# MCU009A_ADC.net
KiCad netlist of a schematic drawn in Altium Designer
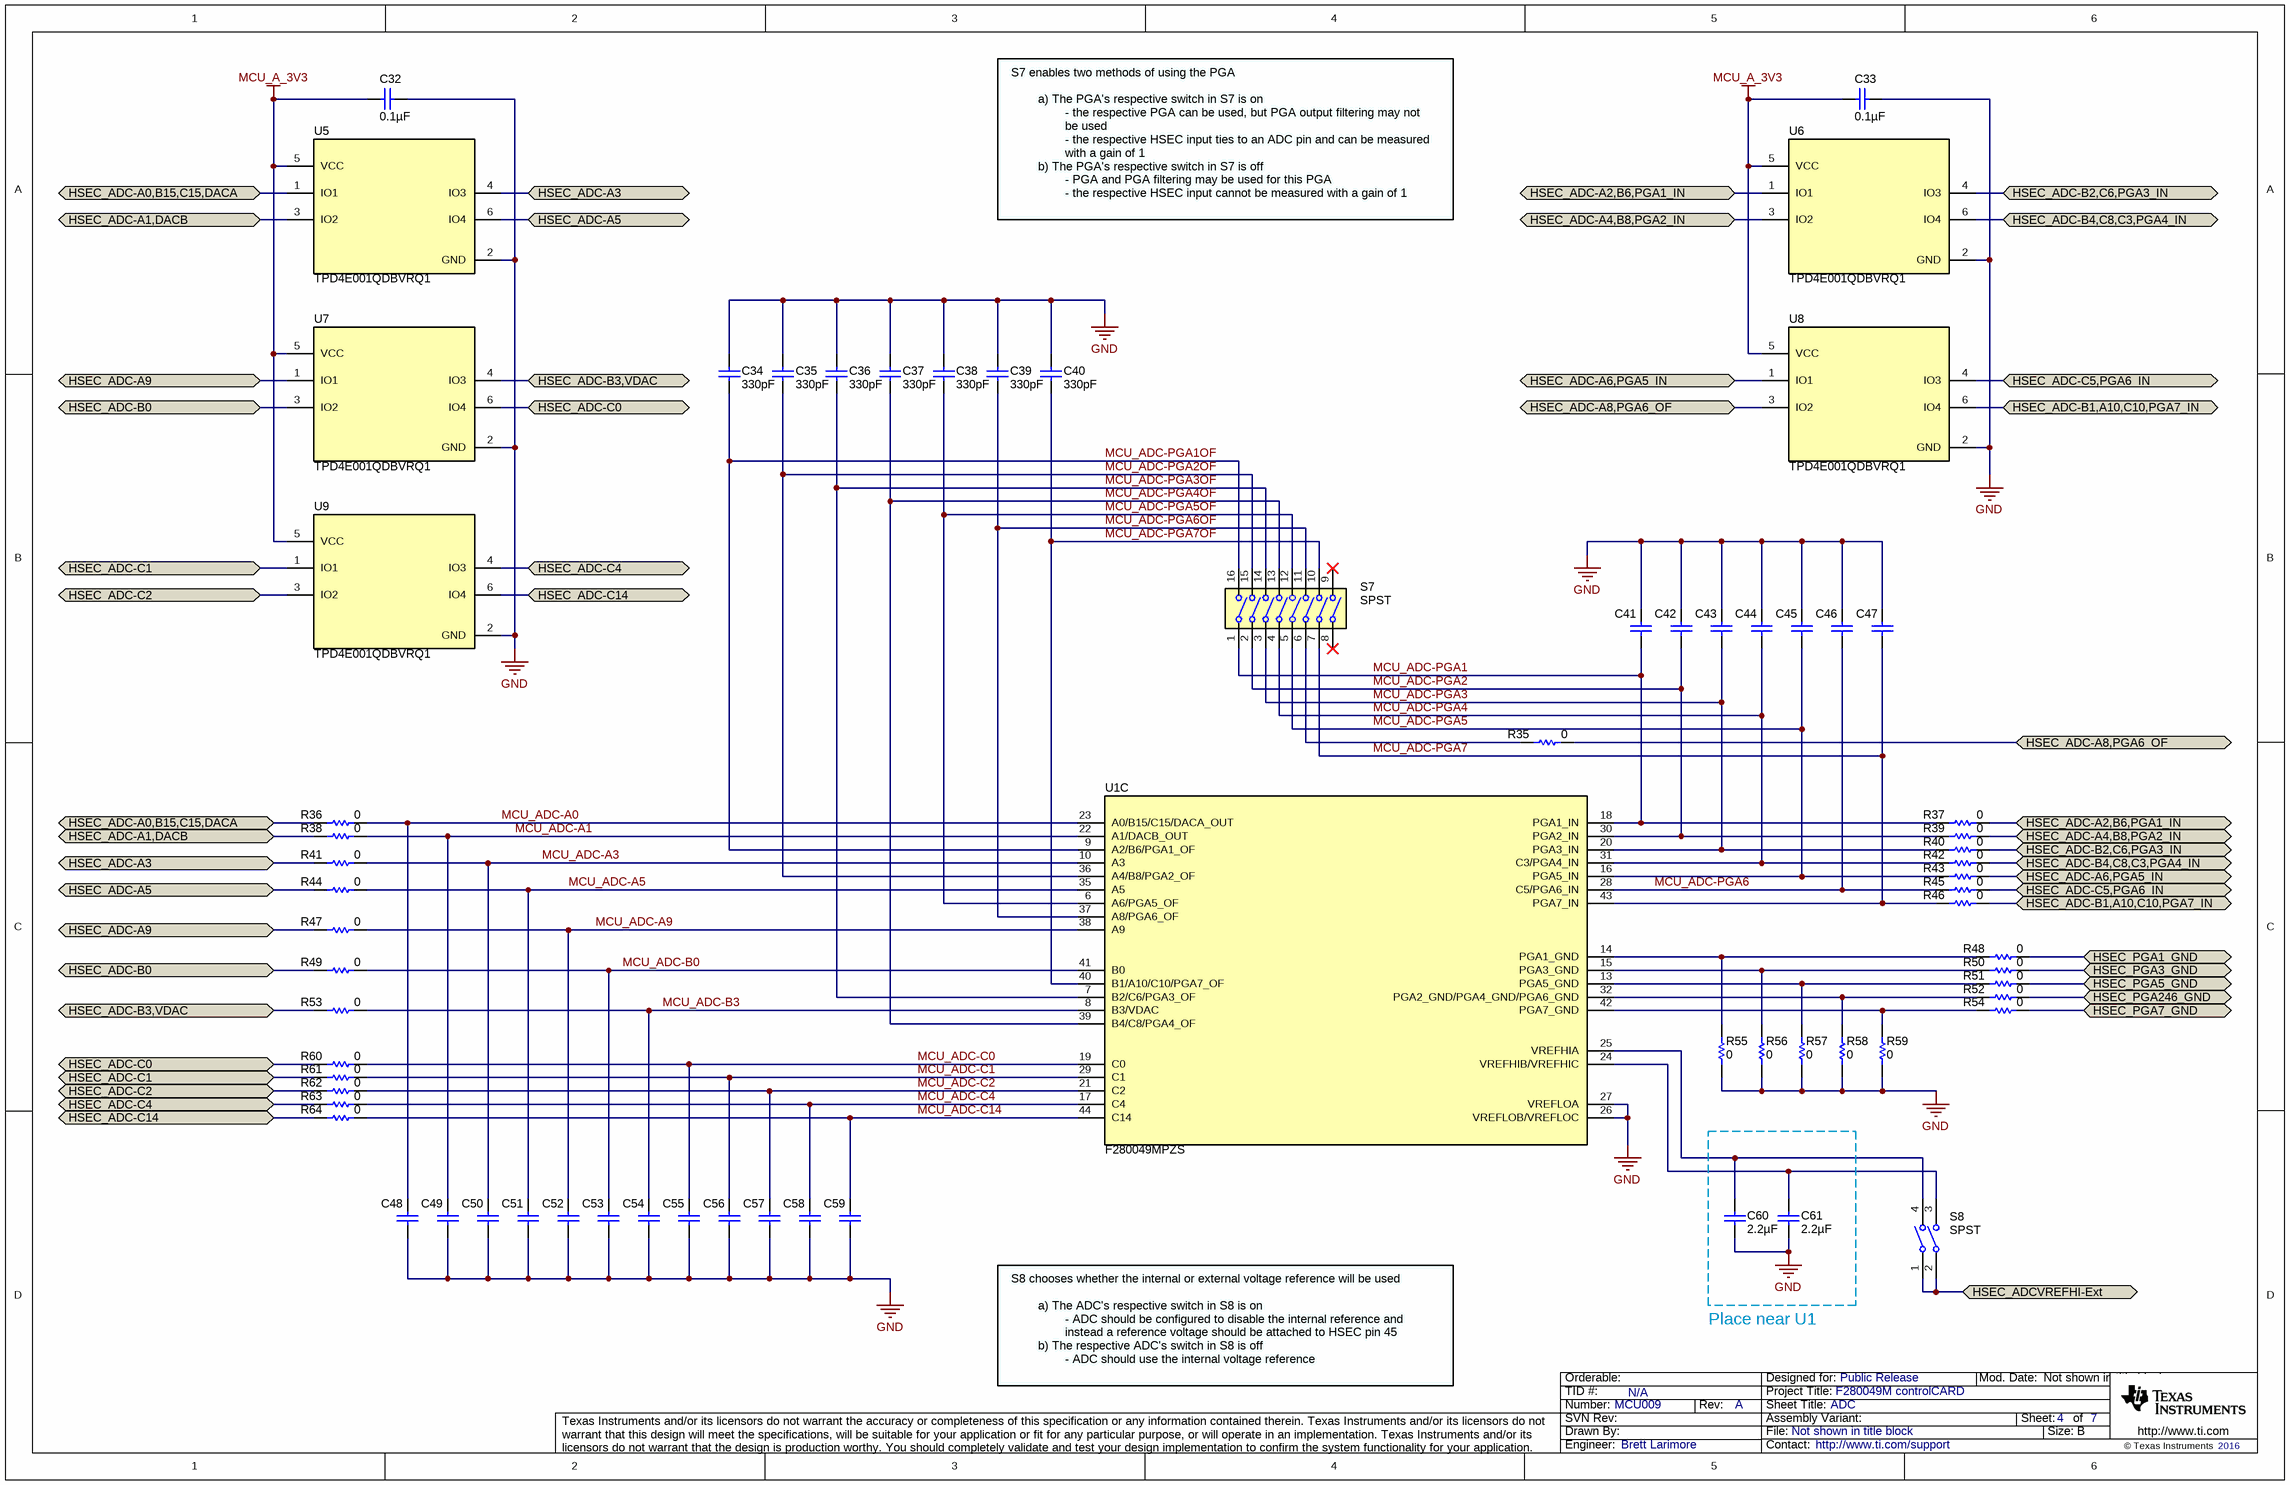
[diagram p0: MCU009A_ADC.SchDoc]

(export (version "E")
  (design (tool "Eeschema 10.0.6"))
  (components
    (comp (ref "C32")
      (value "GRM155R71A104KA01D")
      (footprint "0402")
      (description "CAP, CERM, 0.1 µF, 10 V, +/- 10%, X7R, 0402")
      (fields
        (field (name "VALUEDISPLAYED") "0.1µF")
        (field (name "MANUFACTURER") "MuRata")
        (field (name "PUBLISHER") "Texas Instruments")
      )
      (libsource (lib "Capacitor_Ceramic") (part "GRM155R71A104KA01D"))
    )
    (comp (ref "C33")
      (value "GRM155R71A104KA01D")
      (footprint "0402")
      (description "CAP, CERM, 0.1 µF, 10 V, +/- 10%, X7R, 0402")
      (fields
        (field (name "VALUEDISPLAYED") "0.1µF")
        (field (name "MANUFACTURER") "MuRata")
        (field (name "PUBLISHER") "Texas Instruments")
      )
      (libsource (lib "Capacitor_Ceramic") (part "GRM155R71A104KA01D"))
    )
    (comp (ref "C34")
      (value "GRM1885C1H331JA01D")
      (footprint "0603")
      (description "CAP, CERM, 330 pF, 50 V, +/- 5%, C0G/NP0, 0603")
      (fields
        (field (name "VALUEDISPLAYED") "330pF")
        (field (name "MANUFACTURER") "MuRata")
        (field (name "PUBLISHER") "Texas Instruments")
      )
      (libsource (lib "Capacitor_Ceramic") (part "GRM1885C1H331JA01D"))
    )
    (comp (ref "C35")
      (value "GRM1885C1H331JA01D")
      (footprint "0603")
      (description "CAP, CERM, 330 pF, 50 V, +/- 5%, C0G/NP0, 0603")
      (fields
        (field (name "VALUEDISPLAYED") "330pF")
        (field (name "MANUFACTURER") "MuRata")
        (field (name "PUBLISHER") "Texas Instruments")
      )
      (libsource (lib "Capacitor_Ceramic") (part "GRM1885C1H331JA01D"))
    )
    (comp (ref "C36")
      (value "GRM1885C1H331JA01D")
      (footprint "0603")
      (description "CAP, CERM, 330 pF, 50 V, +/- 5%, C0G/NP0, 0603")
      (fields
        (field (name "VALUEDISPLAYED") "330pF")
        (field (name "MANUFACTURER") "MuRata")
        (field (name "PUBLISHER") "Texas Instruments")
      )
      (libsource (lib "Capacitor_Ceramic") (part "GRM1885C1H331JA01D"))
    )
    (comp (ref "C37")
      (value "GRM1885C1H331JA01D")
      (footprint "0603")
      (description "CAP, CERM, 330 pF, 50 V, +/- 5%, C0G/NP0, 0603")
      (fields
        (field (name "VALUEDISPLAYED") "330pF")
        (field (name "MANUFACTURER") "MuRata")
        (field (name "PUBLISHER") "Texas Instruments")
      )
      (libsource (lib "Capacitor_Ceramic") (part "GRM1885C1H331JA01D"))
    )
    (comp (ref "C38")
      (value "GRM1885C1H331JA01D")
      (footprint "0603")
      (description "CAP, CERM, 330 pF, 50 V, +/- 5%, C0G/NP0, 0603")
      (fields
        (field (name "VALUEDISPLAYED") "330pF")
        (field (name "MANUFACTURER") "MuRata")
        (field (name "PUBLISHER") "Texas Instruments")
      )
      (libsource (lib "Capacitor_Ceramic") (part "GRM1885C1H331JA01D"))
    )
    (comp (ref "C39")
      (value "GRM1885C1H331JA01D")
      (footprint "0603")
      (description "CAP, CERM, 330 pF, 50 V, +/- 5%, C0G/NP0, 0603")
      (fields
        (field (name "VALUEDISPLAYED") "330pF")
        (field (name "MANUFACTURER") "MuRata")
        (field (name "PUBLISHER") "Texas Instruments")
      )
      (libsource (lib "Capacitor_Ceramic") (part "GRM1885C1H331JA01D"))
    )
    (comp (ref "C40")
      (value "GRM1885C1H331JA01D")
      (footprint "0603")
      (description "CAP, CERM, 330 pF, 50 V, +/- 5%, C0G/NP0, 0603")
      (fields
        (field (name "VALUEDISPLAYED") "330pF")
        (field (name "MANUFACTURER") "MuRata")
        (field (name "PUBLISHER") "Texas Instruments")
      )
      (libsource (lib "Capacitor_Ceramic") (part "GRM1885C1H331JA01D"))
    )
    (comp (ref "C41")
      (value "GRM188R71C104KA01D")
      (footprint "0603")
      (description "CAP, CERM, 0.1 µF, 16 V, +/- 10%, X7R, 0603")
      (fields (field (name "MANUFACTURER") "MuRata") (field (name "PUBLISHER") "Texas Instruments"))
      (libsource (lib "Capacitor_Ceramic") (part "GRM188R71C104KA01D"))
    )
    (comp (ref "C42")
      (value "GRM188R71C104KA01D")
      (footprint "0603")
      (description "CAP, CERM, 0.1 µF, 16 V, +/- 10%, X7R, 0603")
      (fields (field (name "MANUFACTURER") "MuRata") (field (name "PUBLISHER") "Texas Instruments"))
      (libsource (lib "Capacitor_Ceramic") (part "GRM188R71C104KA01D"))
    )
    (comp (ref "C43")
      (value "GRM188R71C104KA01D")
      (footprint "0603")
      (description "CAP, CERM, 0.1 µF, 16 V, +/- 10%, X7R, 0603")
      (fields (field (name "MANUFACTURER") "MuRata") (field (name "PUBLISHER") "Texas Instruments"))
      (libsource (lib "Capacitor_Ceramic") (part "GRM188R71C104KA01D"))
    )
    (comp (ref "C44")
      (value "GRM188R71C104KA01D")
      (footprint "0603")
      (description "CAP, CERM, 0.1 µF, 16 V, +/- 10%, X7R, 0603")
      (fields (field (name "MANUFACTURER") "MuRata") (field (name "PUBLISHER") "Texas Instruments"))
      (libsource (lib "Capacitor_Ceramic") (part "GRM188R71C104KA01D"))
    )
    (comp (ref "C45")
      (value "GRM188R71C104KA01D")
      (footprint "0603")
      (description "CAP, CERM, 0.1 µF, 16 V, +/- 10%, X7R, 0603")
      (fields (field (name "MANUFACTURER") "MuRata") (field (name "PUBLISHER") "Texas Instruments"))
      (libsource (lib "Capacitor_Ceramic") (part "GRM188R71C104KA01D"))
    )
    (comp (ref "C46")
      (value "GRM188R71C104KA01D")
      (footprint "0603")
      (description "CAP, CERM, 0.1 µF, 16 V, +/- 10%, X7R, 0603")
      (fields (field (name "MANUFACTURER") "MuRata") (field (name "PUBLISHER") "Texas Instruments"))
      (libsource (lib "Capacitor_Ceramic") (part "GRM188R71C104KA01D"))
    )
    (comp (ref "C47")
      (value "GRM188R71C104KA01D")
      (footprint "0603")
      (description "CAP, CERM, 0.1 µF, 16 V, +/- 10%, X7R, 0603")
      (fields (field (name "MANUFACTURER") "MuRata") (field (name "PUBLISHER") "Texas Instruments"))
      (libsource (lib "Capacitor_Ceramic") (part "GRM188R71C104KA01D"))
    )
    (comp (ref "C48")
      (value "GRM188R71C104KA01D")
      (footprint "0603")
      (description "CAP, CERM, 0.1 µF, 16 V, +/- 10%, X7R, 0603")
      (fields (field (name "MANUFACTURER") "MuRata") (field (name "PUBLISHER") "Texas Instruments"))
      (libsource (lib "Capacitor_Ceramic") (part "GRM188R71C104KA01D"))
    )
    (comp (ref "C49")
      (value "GRM188R71C104KA01D")
      (footprint "0603")
      (description "CAP, CERM, 0.1 µF, 16 V, +/- 10%, X7R, 0603")
      (fields (field (name "MANUFACTURER") "MuRata") (field (name "PUBLISHER") "Texas Instruments"))
      (libsource (lib "Capacitor_Ceramic") (part "GRM188R71C104KA01D"))
    )
    (comp (ref "C50")
      (value "GRM188R71C104KA01D")
      (footprint "0603")
      (description "CAP, CERM, 0.1 µF, 16 V, +/- 10%, X7R, 0603")
      (fields (field (name "MANUFACTURER") "MuRata") (field (name "PUBLISHER") "Texas Instruments"))
      (libsource (lib "Capacitor_Ceramic") (part "GRM188R71C104KA01D"))
    )
    (comp (ref "C51")
      (value "GRM188R71C104KA01D")
      (footprint "0603")
      (description "CAP, CERM, 0.1 µF, 16 V, +/- 10%, X7R, 0603")
      (fields (field (name "MANUFACTURER") "MuRata") (field (name "PUBLISHER") "Texas Instruments"))
      (libsource (lib "Capacitor_Ceramic") (part "GRM188R71C104KA01D"))
    )
    (comp (ref "C52")
      (value "GRM188R71C104KA01D")
      (footprint "0603")
      (description "CAP, CERM, 0.1 µF, 16 V, +/- 10%, X7R, 0603")
      (fields (field (name "MANUFACTURER") "MuRata") (field (name "PUBLISHER") "Texas Instruments"))
      (libsource (lib "Capacitor_Ceramic") (part "GRM188R71C104KA01D"))
    )
    (comp (ref "C53")
      (value "GRM188R71C104KA01D")
      (footprint "0603")
      (description "CAP, CERM, 0.1 µF, 16 V, +/- 10%, X7R, 0603")
      (fields (field (name "MANUFACTURER") "MuRata") (field (name "PUBLISHER") "Texas Instruments"))
      (libsource (lib "Capacitor_Ceramic") (part "GRM188R71C104KA01D"))
    )
    (comp (ref "C54")
      (value "GRM188R71C104KA01D")
      (footprint "0603")
      (description "CAP, CERM, 0.1 µF, 16 V, +/- 10%, X7R, 0603")
      (fields (field (name "MANUFACTURER") "MuRata") (field (name "PUBLISHER") "Texas Instruments"))
      (libsource (lib "Capacitor_Ceramic") (part "GRM188R71C104KA01D"))
    )
    (comp (ref "C55")
      (value "GRM188R71C104KA01D")
      (footprint "0603")
      (description "CAP, CERM, 0.1 µF, 16 V, +/- 10%, X7R, 0603")
      (fields (field (name "MANUFACTURER") "MuRata") (field (name "PUBLISHER") "Texas Instruments"))
      (libsource (lib "Capacitor_Ceramic") (part "GRM188R71C104KA01D"))
    )
    (comp (ref "C56")
      (value "GRM188R71C104KA01D")
      (footprint "0603")
      (description "CAP, CERM, 0.1 µF, 16 V, +/- 10%, X7R, 0603")
      (fields (field (name "MANUFACTURER") "MuRata") (field (name "PUBLISHER") "Texas Instruments"))
      (libsource (lib "Capacitor_Ceramic") (part "GRM188R71C104KA01D"))
    )
    (comp (ref "C57")
      (value "GRM188R71C104KA01D")
      (footprint "0603")
      (description "CAP, CERM, 0.1 µF, 16 V, +/- 10%, X7R, 0603")
      (fields (field (name "MANUFACTURER") "MuRata") (field (name "PUBLISHER") "Texas Instruments"))
      (libsource (lib "Capacitor_Ceramic") (part "GRM188R71C104KA01D"))
    )
    (comp (ref "C58")
      (value "GRM188R71C104KA01D")
      (footprint "0603")
      (description "CAP, CERM, 0.1 µF, 16 V, +/- 10%, X7R, 0603")
      (fields (field (name "MANUFACTURER") "MuRata") (field (name "PUBLISHER") "Texas Instruments"))
      (libsource (lib "Capacitor_Ceramic") (part "GRM188R71C104KA01D"))
    )
    (comp (ref "C59")
      (value "GRM188R71C104KA01D")
      (footprint "0603")
      (description "CAP, CERM, 0.1 µF, 16 V, +/- 10%, X7R, 0603")
      (fields (field (name "MANUFACTURER") "MuRata") (field (name "PUBLISHER") "Texas Instruments"))
      (libsource (lib "Capacitor_Ceramic") (part "GRM188R71C104KA01D"))
    )
    (comp (ref "C60")
      (value "GRM188R61A225KE34D")
      (footprint "0603")
      (description "CAP, CERM, 2.2 µF, 10 V, +/- 10%, X5R, 0603")
      (fields
        (field (name "VALUEDISPLAYED") "2.2µF")
        (field (name "MANUFACTURER") "MuRata")
        (field (name "PUBLISHER") "Texas Instruments")
      )
      (libsource (lib "Capacitor_Ceramic") (part "GRM188R61A225KE34D"))
    )
    (comp (ref "C61")
      (value "GRM188R61A225KE34D")
      (footprint "0603")
      (description "CAP, CERM, 2.2 µF, 10 V, +/- 10%, X5R, 0603")
      (fields
        (field (name "VALUEDISPLAYED") "2.2µF")
        (field (name "MANUFACTURER") "MuRata")
        (field (name "PUBLISHER") "Texas Instruments")
      )
      (libsource (lib "Capacitor_Ceramic") (part "GRM188R61A225KE34D"))
    )
    (comp (ref "R35")
      (value "CRCW06030000Z0EA")
      (footprint "0603")
      (description "RES, 0, 5%, 0.1 W, 0603")
      (fields
        (field (name "VALUEDISPLAYED") "0")
        (field (name "MANUFACTURER") "Vishay-Dale")
        (field (name "PUBLISHER") "Texas Instruments")
      )
      (libsource (lib "Resistor_0603") (part "CRCW06030000Z0EA"))
    )
    (comp (ref "R36")
      (value "CRCW06030000Z0EA")
      (footprint "0603")
      (description "RES, 0, 5%, 0.1 W, 0603")
      (fields
        (field (name "VALUEDISPLAYED") "0")
        (field (name "MANUFACTURER") "Vishay-Dale")
        (field (name "PUBLISHER") "Texas Instruments")
      )
      (libsource (lib "Resistor_0603") (part "CRCW06030000Z0EA"))
    )
    (comp (ref "R37")
      (value "CRCW06030000Z0EA")
      (footprint "0603")
      (description "RES, 0, 5%, 0.1 W, 0603")
      (fields
        (field (name "VALUEDISPLAYED") "0")
        (field (name "MANUFACTURER") "Vishay-Dale")
        (field (name "PUBLISHER") "Texas Instruments")
      )
      (libsource (lib "Resistor_0603") (part "CRCW06030000Z0EA"))
    )
    (comp (ref "R38")
      (value "CRCW06030000Z0EA")
      (footprint "0603")
      (description "RES, 0, 5%, 0.1 W, 0603")
      (fields
        (field (name "VALUEDISPLAYED") "0")
        (field (name "MANUFACTURER") "Vishay-Dale")
        (field (name "PUBLISHER") "Texas Instruments")
      )
      (libsource (lib "Resistor_0603") (part "CRCW06030000Z0EA"))
    )
    (comp (ref "R39")
      (value "CRCW06030000Z0EA")
      (footprint "0603")
      (description "RES, 0, 5%, 0.1 W, 0603")
      (fields
        (field (name "VALUEDISPLAYED") "0")
        (field (name "MANUFACTURER") "Vishay-Dale")
        (field (name "PUBLISHER") "Texas Instruments")
      )
      (libsource (lib "Resistor_0603") (part "CRCW06030000Z0EA"))
    )
    (comp (ref "R40")
      (value "CRCW06030000Z0EA")
      (footprint "0603")
      (description "RES, 0, 5%, 0.1 W, 0603")
      (fields
        (field (name "VALUEDISPLAYED") "0")
        (field (name "MANUFACTURER") "Vishay-Dale")
        (field (name "PUBLISHER") "Texas Instruments")
      )
      (libsource (lib "Resistor_0603") (part "CRCW06030000Z0EA"))
    )
    (comp (ref "R41")
      (value "CRCW06030000Z0EA")
      (footprint "0603")
      (description "RES, 0, 5%, 0.1 W, 0603")
      (fields
        (field (name "VALUEDISPLAYED") "0")
        (field (name "MANUFACTURER") "Vishay-Dale")
        (field (name "PUBLISHER") "Texas Instruments")
      )
      (libsource (lib "Resistor_0603") (part "CRCW06030000Z0EA"))
    )
    (comp (ref "R42")
      (value "CRCW06030000Z0EA")
      (footprint "0603")
      (description "RES, 0, 5%, 0.1 W, 0603")
      (fields
        (field (name "VALUEDISPLAYED") "0")
        (field (name "MANUFACTURER") "Vishay-Dale")
        (field (name "PUBLISHER") "Texas Instruments")
      )
      (libsource (lib "Resistor_0603") (part "CRCW06030000Z0EA"))
    )
    (comp (ref "R43")
      (value "CRCW06030000Z0EA")
      (footprint "0603")
      (description "RES, 0, 5%, 0.1 W, 0603")
      (fields
        (field (name "VALUEDISPLAYED") "0")
        (field (name "MANUFACTURER") "Vishay-Dale")
        (field (name "PUBLISHER") "Texas Instruments")
      )
      (libsource (lib "Resistor_0603") (part "CRCW06030000Z0EA"))
    )
    (comp (ref "R44")
      (value "CRCW06030000Z0EA")
      (footprint "0603")
      (description "RES, 0, 5%, 0.1 W, 0603")
      (fields
        (field (name "VALUEDISPLAYED") "0")
        (field (name "MANUFACTURER") "Vishay-Dale")
        (field (name "PUBLISHER") "Texas Instruments")
      )
      (libsource (lib "Resistor_0603") (part "CRCW06030000Z0EA"))
    )
    (comp (ref "R45")
      (value "CRCW06030000Z0EA")
      (footprint "0603")
      (description "RES, 0, 5%, 0.1 W, 0603")
      (fields
        (field (name "VALUEDISPLAYED") "0")
        (field (name "MANUFACTURER") "Vishay-Dale")
        (field (name "PUBLISHER") "Texas Instruments")
      )
      (libsource (lib "Resistor_0603") (part "CRCW06030000Z0EA"))
    )
    (comp (ref "R46")
      (value "CRCW06030000Z0EA")
      (footprint "0603")
      (description "RES, 0, 5%, 0.1 W, 0603")
      (fields
        (field (name "VALUEDISPLAYED") "0")
        (field (name "MANUFACTURER") "Vishay-Dale")
        (field (name "PUBLISHER") "Texas Instruments")
      )
      (libsource (lib "Resistor_0603") (part "CRCW06030000Z0EA"))
    )
    (comp (ref "R47")
      (value "CRCW06030000Z0EA")
      (footprint "0603")
      (description "RES, 0, 5%, 0.1 W, 0603")
      (fields
        (field (name "VALUEDISPLAYED") "0")
        (field (name "MANUFACTURER") "Vishay-Dale")
        (field (name "PUBLISHER") "Texas Instruments")
      )
      (libsource (lib "Resistor_0603") (part "CRCW06030000Z0EA"))
    )
    (comp (ref "R48")
      (value "CRCW06030000Z0EA")
      (footprint "0603")
      (description "RES, 0, 5%, 0.1 W, 0603")
      (fields
        (field (name "VALUEDISPLAYED") "0")
        (field (name "MANUFACTURER") "Vishay-Dale")
        (field (name "PUBLISHER") "Texas Instruments")
      )
      (libsource (lib "Resistor_0603") (part "CRCW06030000Z0EA"))
    )
    (comp (ref "R49")
      (value "CRCW06030000Z0EA")
      (footprint "0603")
      (description "RES, 0, 5%, 0.1 W, 0603")
      (fields
        (field (name "VALUEDISPLAYED") "0")
        (field (name "MANUFACTURER") "Vishay-Dale")
        (field (name "PUBLISHER") "Texas Instruments")
      )
      (libsource (lib "Resistor_0603") (part "CRCW06030000Z0EA"))
    )
    (comp (ref "R50")
      (value "CRCW06030000Z0EA")
      (footprint "0603")
      (description "RES, 0, 5%, 0.1 W, 0603")
      (fields
        (field (name "VALUEDISPLAYED") "0")
        (field (name "MANUFACTURER") "Vishay-Dale")
        (field (name "PUBLISHER") "Texas Instruments")
      )
      (libsource (lib "Resistor_0603") (part "CRCW06030000Z0EA"))
    )
    (comp (ref "R51")
      (value "CRCW06030000Z0EA")
      (footprint "0603")
      (description "RES, 0, 5%, 0.1 W, 0603")
      (fields
        (field (name "VALUEDISPLAYED") "0")
        (field (name "MANUFACTURER") "Vishay-Dale")
        (field (name "PUBLISHER") "Texas Instruments")
      )
      (libsource (lib "Resistor_0603") (part "CRCW06030000Z0EA"))
    )
    (comp (ref "R52")
      (value "CRCW06030000Z0EA")
      (footprint "0603")
      (description "RES, 0, 5%, 0.1 W, 0603")
      (fields
        (field (name "VALUEDISPLAYED") "0")
        (field (name "MANUFACTURER") "Vishay-Dale")
        (field (name "PUBLISHER") "Texas Instruments")
      )
      (libsource (lib "Resistor_0603") (part "CRCW06030000Z0EA"))
    )
    (comp (ref "R53")
      (value "CRCW06030000Z0EA")
      (footprint "0603")
      (description "RES, 0, 5%, 0.1 W, 0603")
      (fields
        (field (name "VALUEDISPLAYED") "0")
        (field (name "MANUFACTURER") "Vishay-Dale")
        (field (name "PUBLISHER") "Texas Instruments")
      )
      (libsource (lib "Resistor_0603") (part "CRCW06030000Z0EA"))
    )
    (comp (ref "R54")
      (value "CRCW06030000Z0EA")
      (footprint "0603")
      (description "RES, 0, 5%, 0.1 W, 0603")
      (fields
        (field (name "VALUEDISPLAYED") "0")
        (field (name "MANUFACTURER") "Vishay-Dale")
        (field (name "PUBLISHER") "Texas Instruments")
      )
      (libsource (lib "Resistor_0603") (part "CRCW06030000Z0EA"))
    )
    (comp (ref "R55")
      (value "CRCW06030000Z0EA")
      (footprint "0603")
      (description "RES, 0, 5%, 0.1 W, 0603")
      (fields
        (field (name "VALUEDISPLAYED") "0")
        (field (name "MANUFACTURER") "Vishay-Dale")
        (field (name "PUBLISHER") "Texas Instruments")
      )
      (libsource (lib "Resistor_0603") (part "CRCW06030000Z0EA"))
    )
    (comp (ref "R56")
      (value "CRCW06030000Z0EA")
      (footprint "0603")
      (description "RES, 0, 5%, 0.1 W, 0603")
      (fields
        (field (name "VALUEDISPLAYED") "0")
        (field (name "MANUFACTURER") "Vishay-Dale")
        (field (name "PUBLISHER") "Texas Instruments")
      )
      (libsource (lib "Resistor_0603") (part "CRCW06030000Z0EA"))
    )
    (comp (ref "R57")
      (value "CRCW06030000Z0EA")
      (footprint "0603")
      (description "RES, 0, 5%, 0.1 W, 0603")
      (fields
        (field (name "VALUEDISPLAYED") "0")
        (field (name "MANUFACTURER") "Vishay-Dale")
        (field (name "PUBLISHER") "Texas Instruments")
      )
      (libsource (lib "Resistor_0603") (part "CRCW06030000Z0EA"))
    )
    (comp (ref "R58")
      (value "CRCW06030000Z0EA")
      (footprint "0603")
      (description "RES, 0, 5%, 0.1 W, 0603")
      (fields
        (field (name "VALUEDISPLAYED") "0")
        (field (name "MANUFACTURER") "Vishay-Dale")
        (field (name "PUBLISHER") "Texas Instruments")
      )
      (libsource (lib "Resistor_0603") (part "CRCW06030000Z0EA"))
    )
    (comp (ref "R59")
      (value "CRCW06030000Z0EA")
      (footprint "0603")
      (description "RES, 0, 5%, 0.1 W, 0603")
      (fields
        (field (name "VALUEDISPLAYED") "0")
        (field (name "MANUFACTURER") "Vishay-Dale")
        (field (name "PUBLISHER") "Texas Instruments")
      )
      (libsource (lib "Resistor_0603") (part "CRCW06030000Z0EA"))
    )
    (comp (ref "R60")
      (value "CRCW06030000Z0EA")
      (footprint "0603")
      (description "RES, 0, 5%, 0.1 W, 0603")
      (fields
        (field (name "VALUEDISPLAYED") "0")
        (field (name "MANUFACTURER") "Vishay-Dale")
        (field (name "PUBLISHER") "Texas Instruments")
      )
      (libsource (lib "Resistor_0603") (part "CRCW06030000Z0EA"))
    )
    (comp (ref "R61")
      (value "CRCW06030000Z0EA")
      (footprint "0603")
      (description "RES, 0, 5%, 0.1 W, 0603")
      (fields
        (field (name "VALUEDISPLAYED") "0")
        (field (name "MANUFACTURER") "Vishay-Dale")
        (field (name "PUBLISHER") "Texas Instruments")
      )
      (libsource (lib "Resistor_0603") (part "CRCW06030000Z0EA"))
    )
    (comp (ref "R62")
      (value "CRCW06030000Z0EA")
      (footprint "0603")
      (description "RES, 0, 5%, 0.1 W, 0603")
      (fields
        (field (name "VALUEDISPLAYED") "0")
        (field (name "MANUFACTURER") "Vishay-Dale")
        (field (name "PUBLISHER") "Texas Instruments")
      )
      (libsource (lib "Resistor_0603") (part "CRCW06030000Z0EA"))
    )
    (comp (ref "R63")
      (value "CRCW06030000Z0EA")
      (footprint "0603")
      (description "RES, 0, 5%, 0.1 W, 0603")
      (fields
        (field (name "VALUEDISPLAYED") "0")
        (field (name "MANUFACTURER") "Vishay-Dale")
        (field (name "PUBLISHER") "Texas Instruments")
      )
      (libsource (lib "Resistor_0603") (part "CRCW06030000Z0EA"))
    )
    (comp (ref "R64")
      (value "CRCW06030000Z0EA")
      (footprint "0603")
      (description "RES, 0, 5%, 0.1 W, 0603")
      (fields
        (field (name "VALUEDISPLAYED") "0")
        (field (name "MANUFACTURER") "Vishay-Dale")
        (field (name "PUBLISHER") "Texas Instruments")
      )
      (libsource (lib "Resistor_0603") (part "CRCW06030000Z0EA"))
    )
    (comp (ref "S7")
      (value "218-8LPST")
      (footprint "SW_218-8LP")
      (description "Switch, SPST, 8 Pos, 25mA, 24VDC, SMD")
      (fields
        (field (name "MANUFACTURER") "CTS Electrocomponents")
        (field (name "CIRCUIT") "SPST")
        (field (name "SYMBOLCREATOR") "a0412235")
        (field (name "PUBLISHER") "Texas Instruments")
      )
      (libsource (lib "Switches") (part "218-8LPST"))
    )
    (comp (ref "S8")
      (value "218-2LPST")
      (footprint "SW_218-2LP")
      (description "Switch, SPST, 2 Pos, 25mA, 24VDC, SMD")
      (fields
        (field (name "MANUFACTURER") "CTS Electrocomponents")
        (field (name "CIRCUIT") "SPST")
        (field (name "SYMBOLCREATOR") "Altium")
        (field (name "PUBLISHER") "Texas Instruments")
      )
      (libsource (lib "Switches") (part "218-2LPST"))
    )
    (comp (ref "U1")
      (value "F280049MPZS")
      (footprint "PZ0100A_N")
      (description "Piccolo Microcontroller, PZ0100A (LQFP-100)")
      (fields
        (field (name "MANUFACTURER") "Texas Instruments")
        (field (name "SYMBOLCREATOR") "Altium")
        (field (name "PUBLISHER") "Texas Instruments")
      )
      (libsource (lib "TI_Pre_RTM") (part "F280049MPZS"))
    )
    (comp (ref "U5")
      (value "TPD4E001QDBVRQ1")
      (footprint "DBV0006A_N")
      (description "4-CHANNEL ESD PROTECTION ARRAY WITH 1.5-pF IO CAPACITANCE, DBV006A (SOT-6)")
      (fields
        (field (name "MANUFACTURER") "Texas Instruments")
        (field (name "SYMBOLCREATOR") "Altium")
        (field (name "PUBLISHER") "Texas Instruments")
      )
      (libsource (lib "TI_Pre_Release") (part "TPD4E001QDBVRQ1"))
    )
    (comp (ref "U6")
      (value "TPD4E001QDBVRQ1")
      (footprint "DBV0006A_N")
      (description "4-CHANNEL ESD PROTECTION ARRAY WITH 1.5-pF IO CAPACITANCE, DBV006A (SOT-6)")
      (fields
        (field (name "MANUFACTURER") "Texas Instruments")
        (field (name "SYMBOLCREATOR") "Altium")
        (field (name "PUBLISHER") "Texas Instruments")
      )
      (libsource (lib "TI_Pre_Release") (part "TPD4E001QDBVRQ1"))
    )
    (comp (ref "U7")
      (value "TPD4E001QDBVRQ1")
      (footprint "DBV0006A_N")
      (description "4-CHANNEL ESD PROTECTION ARRAY WITH 1.5-pF IO CAPACITANCE, DBV006A (SOT-6)")
      (fields
        (field (name "MANUFACTURER") "Texas Instruments")
        (field (name "SYMBOLCREATOR") "Altium")
        (field (name "PUBLISHER") "Texas Instruments")
      )
      (libsource (lib "TI_Pre_Release") (part "TPD4E001QDBVRQ1"))
    )
    (comp (ref "U8")
      (value "TPD4E001QDBVRQ1")
      (footprint "DBV0006A_N")
      (description "4-CHANNEL ESD PROTECTION ARRAY WITH 1.5-pF IO CAPACITANCE, DBV006A (SOT-6)")
      (fields
        (field (name "MANUFACTURER") "Texas Instruments")
        (field (name "SYMBOLCREATOR") "Altium")
        (field (name "PUBLISHER") "Texas Instruments")
      )
      (libsource (lib "TI_Pre_Release") (part "TPD4E001QDBVRQ1"))
    )
    (comp (ref "U9")
      (value "TPD4E001QDBVRQ1")
      (footprint "DBV0006A_N")
      (description "4-CHANNEL ESD PROTECTION ARRAY WITH 1.5-pF IO CAPACITANCE, DBV006A (SOT-6)")
      (fields
        (field (name "MANUFACTURER") "Texas Instruments")
        (field (name "SYMBOLCREATOR") "Altium")
        (field (name "PUBLISHER") "Texas Instruments")
      )
      (libsource (lib "TI_Pre_Release") (part "TPD4E001QDBVRQ1"))
    )
  )
  (nets
    (net (code "1") (name "/HSEC_ADC-A0,B15,C15,DACA") (class "Default")
      (node (ref "R36") (pin "2") (pinfunction "2_2") (pintype "passive"))
      (node (ref "U5") (pin "1") (pinfunction "IO1_1") (pintype "passive"))
    )
    (net (code "2") (name "/HSEC_ADC-A1,DACB") (class "Default")
      (node (ref "R38") (pin "2") (pinfunction "2_2") (pintype "passive"))
      (node (ref "U5") (pin "3") (pinfunction "IO2_3") (pintype "passive"))
    )
    (net (code "3") (name "/HSEC_ADC-A2,B6,PGA1_IN") (class "Default")
      (node (ref "R37") (pin "1") (pinfunction "1_1") (pintype "passive"))
      (node (ref "U6") (pin "1") (pinfunction "IO1_1") (pintype "passive"))
    )
    (net (code "4") (name "/HSEC_ADC-A3") (class "Default")
      (node (ref "R41") (pin "2") (pinfunction "2_2") (pintype "passive"))
      (node (ref "U5") (pin "4") (pinfunction "IO3_4") (pintype "passive"))
    )
    (net (code "5") (name "/HSEC_ADC-A4,B8,PGA2_IN") (class "Default")
      (node (ref "R39") (pin "1") (pinfunction "1_1") (pintype "passive"))
      (node (ref "U6") (pin "3") (pinfunction "IO2_3") (pintype "passive"))
    )
    (net (code "6") (name "/HSEC_ADC-A5") (class "Default")
      (node (ref "R44") (pin "2") (pinfunction "2_2") (pintype "passive"))
      (node (ref "U5") (pin "6") (pinfunction "IO4_6") (pintype "passive"))
    )
    (net (code "7") (name "/HSEC_ADC-A6,PGA5_IN") (class "Default")
      (node (ref "R43") (pin "1") (pinfunction "1_1") (pintype "passive"))
      (node (ref "U8") (pin "1") (pinfunction "IO1_1") (pintype "passive"))
    )
    (net (code "8") (name "/HSEC_ADC-A8,PGA6_OF") (class "Default")
      (node (ref "R35") (pin "1") (pinfunction "1_1") (pintype "passive"))
      (node (ref "U8") (pin "3") (pinfunction "IO2_3") (pintype "passive"))
    )
    (net (code "9") (name "/HSEC_ADC-A9") (class "Default")
      (node (ref "R47") (pin "2") (pinfunction "2_2") (pintype "passive"))
      (node (ref "U7") (pin "1") (pinfunction "IO1_1") (pintype "passive"))
    )
    (net (code "10") (name "/HSEC_ADC-B0") (class "Default")
      (node (ref "R49") (pin "2") (pinfunction "2_2") (pintype "passive"))
      (node (ref "U7") (pin "3") (pinfunction "IO2_3") (pintype "passive"))
    )
    (net (code "11") (name "/HSEC_ADC-B1,A10,C10,PGA7_IN") (class "Default")
      (node (ref "R46") (pin "1") (pinfunction "1_1") (pintype "passive"))
      (node (ref "U8") (pin "6") (pinfunction "IO4_6") (pintype "passive"))
    )
    (net (code "12") (name "/HSEC_ADC-B2,C6,PGA3_IN") (class "Default")
      (node (ref "R40") (pin "1") (pinfunction "1_1") (pintype "passive"))
      (node (ref "U6") (pin "4") (pinfunction "IO3_4") (pintype "passive"))
    )
    (net (code "13") (name "/HSEC_ADC-B3,VDAC") (class "Default")
      (node (ref "R53") (pin "2") (pinfunction "2_2") (pintype "passive"))
      (node (ref "U7") (pin "4") (pinfunction "IO3_4") (pintype "passive"))
    )
    (net (code "14") (name "/HSEC_ADC-B4,C8,C3,PGA4_IN") (class "Default")
      (node (ref "R42") (pin "1") (pinfunction "1_1") (pintype "passive"))
      (node (ref "U6") (pin "6") (pinfunction "IO4_6") (pintype "passive"))
    )
    (net (code "15") (name "/HSEC_ADC-C0") (class "Default")
      (node (ref "R60") (pin "2") (pinfunction "2_2") (pintype "passive"))
      (node (ref "U7") (pin "6") (pinfunction "IO4_6") (pintype "passive"))
    )
    (net (code "16") (name "/HSEC_ADC-C1") (class "Default")
      (node (ref "R61") (pin "2") (pinfunction "2_2") (pintype "passive"))
      (node (ref "U9") (pin "1") (pinfunction "IO1_1") (pintype "passive"))
    )
    (net (code "17") (name "/HSEC_ADC-C2") (class "Default")
      (node (ref "R62") (pin "2") (pinfunction "2_2") (pintype "passive"))
      (node (ref "U9") (pin "3") (pinfunction "IO2_3") (pintype "passive"))
    )
    (net (code "18") (name "/HSEC_ADC-C4") (class "Default")
      (node (ref "R63") (pin "2") (pinfunction "2_2") (pintype "passive"))
      (node (ref "U9") (pin "4") (pinfunction "IO3_4") (pintype "passive"))
    )
    (net (code "19") (name "/HSEC_ADC-C5,PGA6_IN") (class "Default")
      (node (ref "R45") (pin "1") (pinfunction "1_1") (pintype "passive"))
      (node (ref "U8") (pin "4") (pinfunction "IO3_4") (pintype "passive"))
    )
    (net (code "20") (name "/HSEC_ADC-C14") (class "Default")
      (node (ref "R64") (pin "2") (pinfunction "2_2") (pintype "passive"))
      (node (ref "U9") (pin "6") (pinfunction "IO4_6") (pintype "passive"))
    )
    (net (code "21") (name "/HSEC_ADCVREFHI-Ext") (class "Default")
      (node (ref "S8") (pin "1") (pinfunction "1_1") (pintype "passive"))
      (node (ref "S8") (pin "2") (pinfunction "2_2") (pintype "passive"))
    )
    (net (code "22") (name "/HSEC_PGA1_GND") (class "Default")
      (node (ref "R48") (pin "1") (pinfunction "1_1") (pintype "passive"))
    )
    (net (code "23") (name "/HSEC_PGA3_GND") (class "Default")
      (node (ref "R50") (pin "1") (pinfunction "1_1") (pintype "passive"))
    )
    (net (code "24") (name "/HSEC_PGA5_GND") (class "Default")
      (node (ref "R51") (pin "1") (pinfunction "1_1") (pintype "passive"))
    )
    (net (code "25") (name "/HSEC_PGA7_GND") (class "Default")
      (node (ref "R54") (pin "1") (pinfunction "1_1") (pintype "passive"))
    )
    (net (code "26") (name "/HSEC_PGA246_GND") (class "Default")
      (node (ref "R52") (pin "1") (pinfunction "1_1") (pintype "passive"))
    )
    (net (code "27") (name "/MCU_ADC-A0") (class "Default")
      (node (ref "C48") (pin "1") (pinfunction "1_1") (pintype "passive"))
      (node (ref "R36") (pin "1") (pinfunction "1_1") (pintype "passive"))
      (node (ref "U1") (pin "23") (pinfunction "A0/B15/C15/DACA_OUT_23") (pintype "passive"))
    )
    (net (code "28") (name "/MCU_ADC-A1") (class "Default")
      (node (ref "C49") (pin "1") (pinfunction "1_1") (pintype "passive"))
      (node (ref "R38") (pin "1") (pinfunction "1_1") (pintype "passive"))
      (node (ref "U1") (pin "22") (pinfunction "A1/DACB_OUT_22") (pintype "passive"))
    )
    (net (code "29") (name "/MCU_ADC-A3") (class "Default")
      (node (ref "C50") (pin "1") (pinfunction "1_1") (pintype "passive"))
      (node (ref "R41") (pin "1") (pinfunction "1_1") (pintype "passive"))
      (node (ref "U1") (pin "10") (pinfunction "A3_10") (pintype "passive"))
    )
    (net (code "30") (name "/MCU_ADC-A5") (class "Default")
      (node (ref "C51") (pin "1") (pinfunction "1_1") (pintype "passive"))
      (node (ref "R44") (pin "1") (pinfunction "1_1") (pintype "passive"))
      (node (ref "U1") (pin "35") (pinfunction "A5_35") (pintype "passive"))
    )
    (net (code "31") (name "/MCU_ADC-A9") (class "Default")
      (node (ref "C52") (pin "1") (pinfunction "1_1") (pintype "passive"))
      (node (ref "R47") (pin "1") (pinfunction "1_1") (pintype "passive"))
      (node (ref "U1") (pin "38") (pinfunction "A9_38") (pintype "passive"))
    )
    (net (code "32") (name "/MCU_ADC-B0") (class "Default")
      (node (ref "C53") (pin "1") (pinfunction "1_1") (pintype "passive"))
      (node (ref "R49") (pin "1") (pinfunction "1_1") (pintype "passive"))
      (node (ref "U1") (pin "41") (pinfunction "B0_41") (pintype "passive"))
    )
    (net (code "33") (name "/MCU_ADC-B3") (class "Default")
      (node (ref "C54") (pin "1") (pinfunction "1_1") (pintype "passive"))
      (node (ref "R53") (pin "1") (pinfunction "1_1") (pintype "passive"))
      (node (ref "U1") (pin "8") (pinfunction "B3/VDAC_8") (pintype "passive"))
    )
    (net (code "34") (name "/MCU_ADC-C0") (class "Default")
      (node (ref "C55") (pin "1") (pinfunction "1_1") (pintype "passive"))
      (node (ref "R60") (pin "1") (pinfunction "1_1") (pintype "passive"))
      (node (ref "U1") (pin "19") (pinfunction "C0_19") (pintype "passive"))
    )
    (net (code "35") (name "/MCU_ADC-C1") (class "Default")
      (node (ref "C56") (pin "1") (pinfunction "1_1") (pintype "passive"))
      (node (ref "R61") (pin "1") (pinfunction "1_1") (pintype "passive"))
      (node (ref "U1") (pin "29") (pinfunction "C1_29") (pintype "passive"))
    )
    (net (code "36") (name "/MCU_ADC-C2") (class "Default")
      (node (ref "C57") (pin "1") (pinfunction "1_1") (pintype "passive"))
      (node (ref "R62") (pin "1") (pinfunction "1_1") (pintype "passive"))
      (node (ref "U1") (pin "21") (pinfunction "C2_21") (pintype "passive"))
    )
    (net (code "37") (name "/MCU_ADC-C4") (class "Default")
      (node (ref "C58") (pin "1") (pinfunction "1_1") (pintype "passive"))
      (node (ref "R63") (pin "1") (pinfunction "1_1") (pintype "passive"))
      (node (ref "U1") (pin "17") (pinfunction "C4_17") (pintype "passive"))
    )
    (net (code "38") (name "/MCU_ADC-C14") (class "Default")
      (node (ref "C59") (pin "1") (pinfunction "1_1") (pintype "passive"))
      (node (ref "R64") (pin "1") (pinfunction "1_1") (pintype "passive"))
      (node (ref "U1") (pin "44") (pinfunction "C14_44") (pintype "passive"))
    )
    (net (code "39") (name "/MCU_ADC-PGA1") (class "Default")
      (node (ref "C41") (pin "2") (pinfunction "2_2") (pintype "passive"))
      (node (ref "R37") (pin "2") (pinfunction "2_2") (pintype "passive"))
      (node (ref "S7") (pin "1") (pinfunction "1_1") (pintype "passive"))
      (node (ref "U1") (pin "18") (pinfunction "PGA1_IN_18") (pintype "passive"))
    )
    (net (code "40") (name "/MCU_ADC-PGA1OF") (class "Default")
      (node (ref "C34") (pin "2") (pinfunction "2_2") (pintype "passive"))
      (node (ref "S7") (pin "16") (pinfunction "1A_16") (pintype "passive"))
      (node (ref "U1") (pin "9") (pinfunction "A2/B6/PGA1_OF_9") (pintype "passive"))
    )
    (net (code "41") (name "/MCU_ADC-PGA2") (class "Default")
      (node (ref "C42") (pin "2") (pinfunction "2_2") (pintype "passive"))
      (node (ref "R39") (pin "2") (pinfunction "2_2") (pintype "passive"))
      (node (ref "S7") (pin "2") (pinfunction "2_2") (pintype "passive"))
      (node (ref "U1") (pin "30") (pinfunction "PGA2_IN_30") (pintype "passive"))
    )
    (net (code "42") (name "/MCU_ADC-PGA2OF") (class "Default")
      (node (ref "C35") (pin "2") (pinfunction "2_2") (pintype "passive"))
      (node (ref "S7") (pin "15") (pinfunction "2A_15") (pintype "passive"))
      (node (ref "U1") (pin "36") (pinfunction "A4/B8/PGA2_OF_36") (pintype "passive"))
    )
    (net (code "43") (name "/MCU_ADC-PGA3") (class "Default")
      (node (ref "C43") (pin "2") (pinfunction "2_2") (pintype "passive"))
      (node (ref "R40") (pin "2") (pinfunction "2_2") (pintype "passive"))
      (node (ref "S7") (pin "3") (pinfunction "3_3") (pintype "passive"))
      (node (ref "U1") (pin "20") (pinfunction "PGA3_IN_20") (pintype "passive"))
    )
    (net (code "44") (name "/MCU_ADC-PGA3OF") (class "Default")
      (node (ref "C36") (pin "2") (pinfunction "2_2") (pintype "passive"))
      (node (ref "S7") (pin "14") (pinfunction "3A_14") (pintype "passive"))
      (node (ref "U1") (pin "7") (pinfunction "B2/C6/PGA3_OF_7") (pintype "passive"))
    )
    (net (code "45") (name "/MCU_ADC-PGA4") (class "Default")
      (node (ref "C44") (pin "2") (pinfunction "2_2") (pintype "passive"))
      (node (ref "R42") (pin "2") (pinfunction "2_2") (pintype "passive"))
      (node (ref "S7") (pin "4") (pinfunction "4_4") (pintype "passive"))
      (node (ref "U1") (pin "31") (pinfunction "C3/PGA4_IN_31") (pintype "passive"))
    )
    (net (code "46") (name "/MCU_ADC-PGA4OF") (class "Default")
      (node (ref "C37") (pin "2") (pinfunction "2_2") (pintype "passive"))
      (node (ref "S7") (pin "13") (pinfunction "4A_13") (pintype "passive"))
      (node (ref "U1") (pin "39") (pinfunction "B4/C8/PGA4_OF_39") (pintype "passive"))
    )
    (net (code "47") (name "/MCU_ADC-PGA5") (class "Default")
      (node (ref "C45") (pin "2") (pinfunction "2_2") (pintype "passive"))
      (node (ref "R43") (pin "2") (pinfunction "2_2") (pintype "passive"))
      (node (ref "S7") (pin "5") (pinfunction "5_5") (pintype "passive"))
      (node (ref "U1") (pin "16") (pinfunction "PGA5_IN_16") (pintype "passive"))
    )
    (net (code "48") (name "/MCU_ADC-PGA5OF") (class "Default")
      (node (ref "C38") (pin "2") (pinfunction "2_2") (pintype "passive"))
      (node (ref "S7") (pin "12") (pinfunction "5A_12") (pintype "passive"))
      (node (ref "U1") (pin "6") (pinfunction "A6/PGA5_OF_6") (pintype "passive"))
    )
    (net (code "49") (name "/MCU_ADC-PGA6") (class "Default")
      (node (ref "C46") (pin "2") (pinfunction "2_2") (pintype "passive"))
      (node (ref "R45") (pin "2") (pinfunction "2_2") (pintype "passive"))
      (node (ref "U1") (pin "28") (pinfunction "C5/PGA6_IN_28") (pintype "passive"))
    )
    (net (code "50") (name "/MCU_ADC-PGA6OF") (class "Default")
      (node (ref "C39") (pin "2") (pinfunction "2_2") (pintype "passive"))
      (node (ref "S7") (pin "11") (pinfunction "6A_11") (pintype "passive"))
      (node (ref "U1") (pin "37") (pinfunction "A8/PGA6_OF_37") (pintype "passive"))
    )
    (net (code "51") (name "/MCU_ADC-PGA7") (class "Default")
      (node (ref "C47") (pin "2") (pinfunction "2_2") (pintype "passive"))
      (node (ref "R46") (pin "2") (pinfunction "2_2") (pintype "passive"))
      (node (ref "S7") (pin "7") (pinfunction "7_7") (pintype "passive"))
      (node (ref "U1") (pin "43") (pinfunction "PGA7_IN_43") (pintype "passive"))
    )
    (net (code "52") (name "/MCU_ADC-PGA7OF") (class "Default")
      (node (ref "C40") (pin "2") (pinfunction "2_2") (pintype "passive"))
      (node (ref "S7") (pin "10") (pinfunction "7A_10") (pintype "passive"))
      (node (ref "U1") (pin "40") (pinfunction "B1/A10/C10/PGA7_OF_40") (pintype "passive"))
    )
    (net (code "53") (name "GND") (class "Default")
      (node (ref "C32") (pin "2") (pinfunction "2_2") (pintype "passive"))
      (node (ref "C33") (pin "2") (pinfunction "2_2") (pintype "passive"))
      (node (ref "C34") (pin "1") (pinfunction "1_1") (pintype "passive"))
      (node (ref "C35") (pin "1") (pinfunction "1_1") (pintype "passive"))
      (node (ref "C36") (pin "1") (pinfunction "1_1") (pintype "passive"))
      (node (ref "C37") (pin "1") (pinfunction "1_1") (pintype "passive"))
      (node (ref "C38") (pin "1") (pinfunction "1_1") (pintype "passive"))
      (node (ref "C39") (pin "1") (pinfunction "1_1") (pintype "passive"))
      (node (ref "C40") (pin "1") (pinfunction "1_1") (pintype "passive"))
      (node (ref "C41") (pin "1") (pinfunction "1_1") (pintype "passive"))
      (node (ref "C42") (pin "1") (pinfunction "1_1") (pintype "passive"))
      (node (ref "C43") (pin "1") (pinfunction "1_1") (pintype "passive"))
      (node (ref "C44") (pin "1") (pinfunction "1_1") (pintype "passive"))
      (node (ref "C45") (pin "1") (pinfunction "1_1") (pintype "passive"))
      (node (ref "C46") (pin "1") (pinfunction "1_1") (pintype "passive"))
      (node (ref "C47") (pin "1") (pinfunction "1_1") (pintype "passive"))
      (node (ref "C48") (pin "2") (pinfunction "2_2") (pintype "passive"))
      (node (ref "C49") (pin "2") (pinfunction "2_2") (pintype "passive"))
      (node (ref "C50") (pin "2") (pinfunction "2_2") (pintype "passive"))
      (node (ref "C51") (pin "2") (pinfunction "2_2") (pintype "passive"))
      (node (ref "C52") (pin "2") (pinfunction "2_2") (pintype "passive"))
      (node (ref "C53") (pin "2") (pinfunction "2_2") (pintype "passive"))
      (node (ref "C54") (pin "2") (pinfunction "2_2") (pintype "passive"))
      (node (ref "C55") (pin "2") (pinfunction "2_2") (pintype "passive"))
      (node (ref "C56") (pin "2") (pinfunction "2_2") (pintype "passive"))
      (node (ref "C57") (pin "2") (pinfunction "2_2") (pintype "passive"))
      (node (ref "C58") (pin "2") (pinfunction "2_2") (pintype "passive"))
      (node (ref "C59") (pin "2") (pinfunction "2_2") (pintype "passive"))
      (node (ref "C60") (pin "1") (pinfunction "1_1") (pintype "passive"))
      (node (ref "C61") (pin "1") (pinfunction "1_1") (pintype "passive"))
      (node (ref "R55") (pin "1") (pinfunction "1_1") (pintype "passive"))
      (node (ref "R56") (pin "1") (pinfunction "1_1") (pintype "passive"))
      (node (ref "R57") (pin "1") (pinfunction "1_1") (pintype "passive"))
      (node (ref "R58") (pin "1") (pinfunction "1_1") (pintype "passive"))
      (node (ref "R59") (pin "1") (pinfunction "1_1") (pintype "passive"))
      (node (ref "U1") (pin "26") (pinfunction "VREFLOB/VREFLOC_26") (pintype "passive"))
      (node (ref "U1") (pin "27") (pinfunction "VREFLOA_27") (pintype "passive"))
      (node (ref "U5") (pin "2") (pinfunction "GND_2") (pintype "power_in"))
      (node (ref "U6") (pin "2") (pinfunction "GND_2") (pintype "power_in"))
      (node (ref "U7") (pin "2") (pinfunction "GND_2") (pintype "power_in"))
      (node (ref "U8") (pin "2") (pinfunction "GND_2") (pintype "power_in"))
      (node (ref "U9") (pin "2") (pinfunction "GND_2") (pintype "power_in"))
    )
    (net (code "54") (name "MCU_A_3V3") (class "Default")
      (node (ref "C32") (pin "1") (pinfunction "1_1") (pintype "passive"))
      (node (ref "C33") (pin "1") (pinfunction "1_1") (pintype "passive"))
      (node (ref "U5") (pin "5") (pinfunction "VCC_5") (pintype "power_in"))
      (node (ref "U6") (pin "5") (pinfunction "VCC_5") (pintype "power_in"))
      (node (ref "U7") (pin "5") (pinfunction "VCC_5") (pintype "power_in"))
      (node (ref "U8") (pin "5") (pinfunction "VCC_5") (pintype "power_in"))
      (node (ref "U9") (pin "5") (pinfunction "VCC_5") (pintype "power_in"))
    )
    (net (code "55") (name "Net-(R35-Pad2)") (class "Default")
      (node (ref "R35") (pin "2") (pinfunction "2_2") (pintype "passive"))
      (node (ref "S7") (pin "6") (pinfunction "6_6") (pintype "passive"))
    )
    (net (code "56") (name "Net-(U1C-PGA1_GND)") (class "Default")
      (node (ref "R48") (pin "2") (pinfunction "2_2") (pintype "passive"))
      (node (ref "R55") (pin "2") (pinfunction "2_2") (pintype "passive"))
      (node (ref "U1") (pin "14") (pinfunction "PGA1_GND_14") (pintype "passive"))
    )
    (net (code "57") (name "Net-(U1C-PGA2_GND{slash}PGA4_GND{slash}PGA6_GND)") (class "Default")
      (node (ref "R52") (pin "2") (pinfunction "2_2") (pintype "passive"))
      (node (ref "R58") (pin "2") (pinfunction "2_2") (pintype "passive"))
      (node (ref "U1") (pin "32") (pinfunction "PGA2_GND/PGA4_GND/PGA6_GND_32") (pintype "passive"))
    )
    (net (code "58") (name "Net-(U1C-PGA3_GND)") (class "Default")
      (node (ref "R50") (pin "2") (pinfunction "2_2") (pintype "passive"))
      (node (ref "R56") (pin "2") (pinfunction "2_2") (pintype "passive"))
      (node (ref "U1") (pin "15") (pinfunction "PGA3_GND_15") (pintype "passive"))
    )
    (net (code "59") (name "Net-(U1C-PGA5_GND)") (class "Default")
      (node (ref "R51") (pin "2") (pinfunction "2_2") (pintype "passive"))
      (node (ref "R57") (pin "2") (pinfunction "2_2") (pintype "passive"))
      (node (ref "U1") (pin "13") (pinfunction "PGA5_GND_13") (pintype "passive"))
    )
    (net (code "60") (name "Net-(U1C-PGA7_GND)") (class "Default")
      (node (ref "R54") (pin "2") (pinfunction "2_2") (pintype "passive"))
      (node (ref "R59") (pin "2") (pinfunction "2_2") (pintype "passive"))
      (node (ref "U1") (pin "42") (pinfunction "PGA7_GND_42") (pintype "passive"))
    )
    (net (code "61") (name "Net-(U1C-VREFHIA)") (class "Default")
      (node (ref "C60") (pin "2") (pinfunction "2_2") (pintype "passive"))
      (node (ref "S8") (pin "4") (pinfunction "4_4") (pintype "passive"))
      (node (ref "U1") (pin "25") (pinfunction "VREFHIA_25") (pintype "passive"))
    )
    (net (code "62") (name "Net-(U1C-VREFHIB{slash}VREFHIC)") (class "Default")
      (node (ref "C61") (pin "2") (pinfunction "2_2") (pintype "passive"))
      (node (ref "S8") (pin "3") (pinfunction "3_3") (pintype "passive"))
      (node (ref "U1") (pin "24") (pinfunction "VREFHIB/VREFHIC_24") (pintype "passive"))
    )
    (net (code "63") (name "unconnected-(S7-8A-Pad9)") (class "Default")
      (node (ref "S7") (pin "9") (pinfunction "8A_9") (pintype "passive+no_connect"))
    )
    (net (code "64") (name "unconnected-(S7-Pad8)") (class "Default")
      (node (ref "S7") (pin "8") (pinfunction "8_8") (pintype "passive+no_connect"))
    )
  )
)
